# DDR3_2.net
KiCad netlist of a schematic drawn in Altium Designer
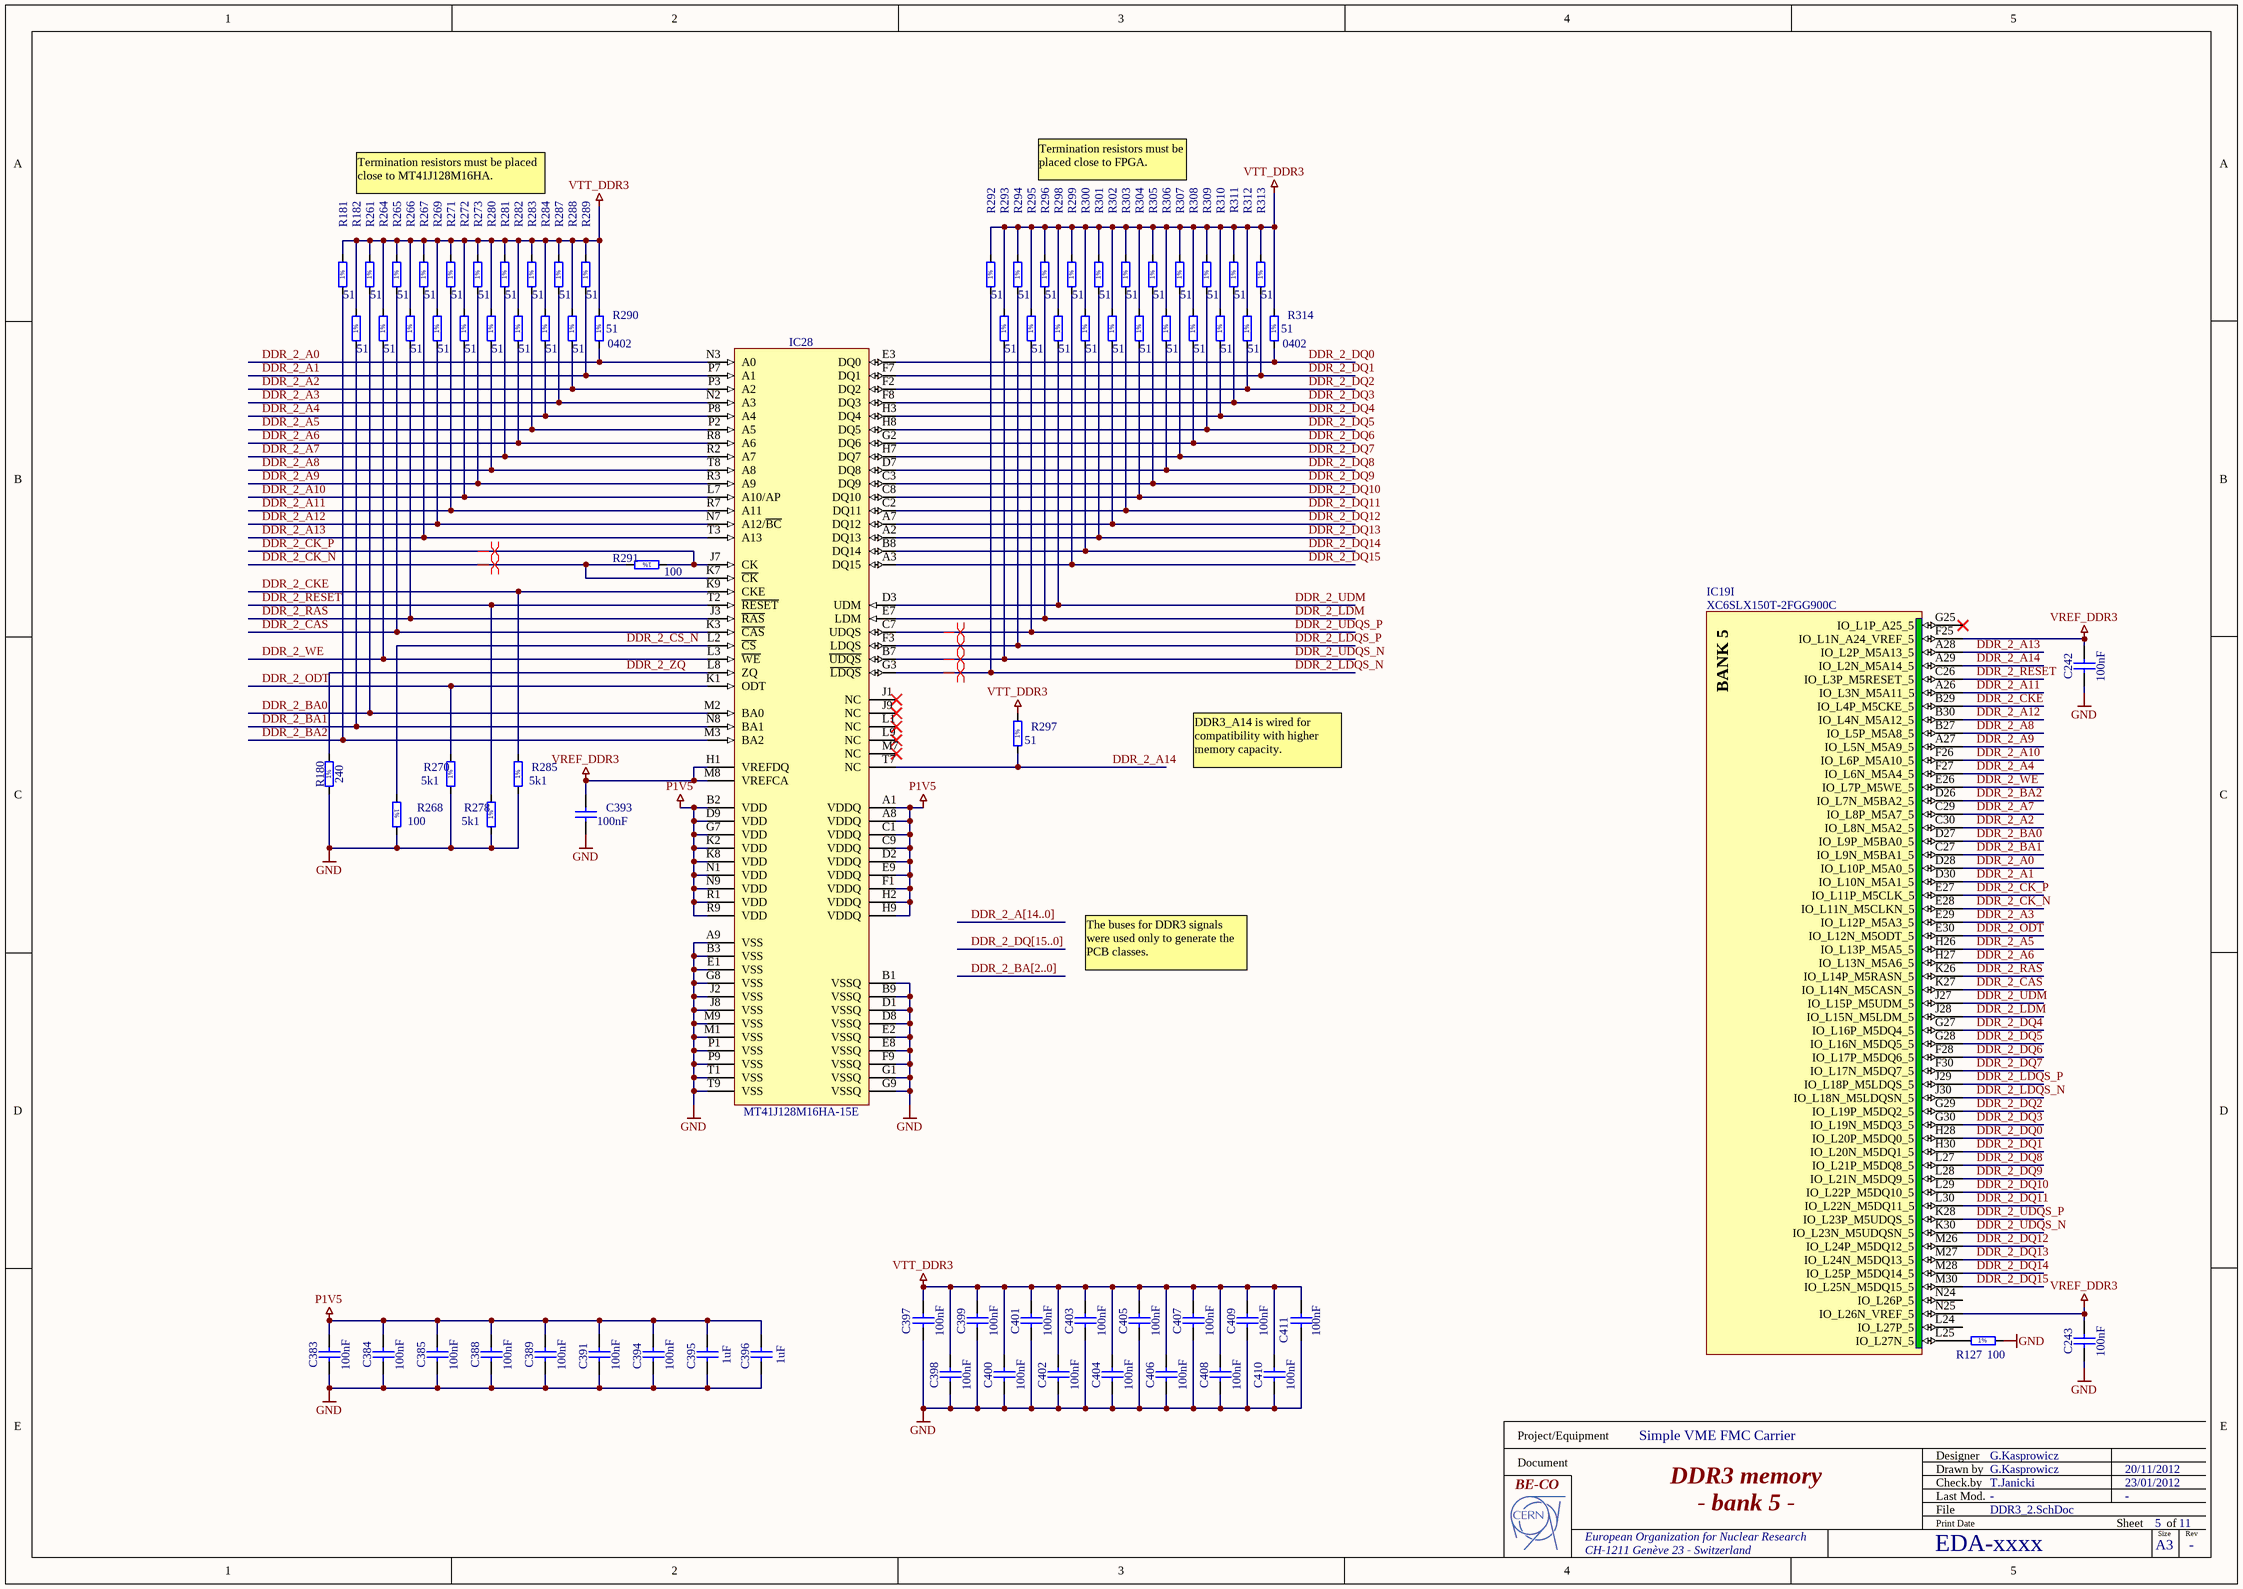
[diagram p0: DDR3_2.SchDoc]

(export (version "E")
  (design (tool "Eeschema 10.0.6"))
  (components
    (comp (ref "C242")
      (value "100nF")
      (footprint "CAPC1005X55N")
      (description "Non-polarised capacitor")
      (fields (field (name "PART NUMBER") "CC0402_100NF_16V_10%_X7R") (field (name "VOLTAGE") "16V"))
      (libsource (lib "Capacitors") (part "Capacitor - non polarized"))
    )
    (comp (ref "C243")
      (value "100nF")
      (footprint "CAPC1005X55N")
      (description "Non-polarised capacitor")
      (fields (field (name "PART NUMBER") "CC0402_100NF_16V_10%_X7R") (field (name "VOLTAGE") "16V"))
      (libsource (lib "Capacitors") (part "Capacitor - non polarized"))
    )
    (comp (ref "C383")
      (value "100nF")
      (footprint "CAPC1005X55N")
      (description "Non-polarised capacitor")
      (fields (field (name "PART NUMBER") "CC0402_100NF_16V_10%_X7R") (field (name "VOLTAGE") "16V"))
      (libsource (lib "Capacitors") (part "Capacitor - non polarized"))
    )
    (comp (ref "C384")
      (value "100nF")
      (footprint "CAPC1005X55N")
      (description "Non-polarised capacitor")
      (fields (field (name "PART NUMBER") "CC0402_100NF_16V_10%_X7R") (field (name "VOLTAGE") "16V"))
      (libsource (lib "Capacitors") (part "Capacitor - non polarized"))
    )
    (comp (ref "C385")
      (value "100nF")
      (footprint "CAPC1005X55N")
      (description "Non-polarised capacitor")
      (fields (field (name "PART NUMBER") "CC0402_100NF_16V_10%_X7R") (field (name "VOLTAGE") "16V"))
      (libsource (lib "Capacitors") (part "Capacitor - non polarized"))
    )
    (comp (ref "C388")
      (value "100nF")
      (footprint "CAPC1005X55N")
      (description "Non-polarised capacitor")
      (fields (field (name "PART NUMBER") "CC0402_100NF_16V_10%_X7R") (field (name "VOLTAGE") "16V"))
      (libsource (lib "Capacitors") (part "Capacitor - non polarized"))
    )
    (comp (ref "C389")
      (value "100nF")
      (footprint "CAPC1005X55N")
      (description "Non-polarised capacitor")
      (fields (field (name "PART NUMBER") "CC0402_100NF_16V_10%_X7R") (field (name "VOLTAGE") "16V"))
      (libsource (lib "Capacitors") (part "Capacitor - non polarized"))
    )
    (comp (ref "C391")
      (value "100nF")
      (footprint "CAPC1005X55N")
      (description "Non-polarised capacitor")
      (fields (field (name "PART NUMBER") "CC0402_100NF_16V_10%_X7R") (field (name "VOLTAGE") "16V"))
      (libsource (lib "Capacitors") (part "Capacitor - non polarized"))
    )
    (comp (ref "C393")
      (value "100nF")
      (footprint "CAPC1005X55N")
      (description "Non-polarised capacitor")
      (fields (field (name "PART NUMBER") "CC0402_100NF_16V_10%_X7R") (field (name "VOLTAGE") "16V"))
      (libsource (lib "Capacitors") (part "Capacitor - non polarized"))
    )
    (comp (ref "C394")
      (value "100nF")
      (footprint "CAPC1005X55N")
      (description "Non-polarised capacitor")
      (fields (field (name "PART NUMBER") "CC0402_100NF_16V_10%_X7R") (field (name "VOLTAGE") "16V"))
      (libsource (lib "Capacitors") (part "Capacitor - non polarized"))
    )
    (comp (ref "C395")
      (value "1uF")
      (footprint "CAPC1608X87N")
      (description "Non-polarised capacitor")
      (fields (field (name "PART NUMBER") "CC0603_1UF_16V_10%_X7R") (field (name "VOLTAGE") "16V"))
      (libsource (lib "Capacitors") (part "Capacitor - non polarized"))
    )
    (comp (ref "C396")
      (value "1uF")
      (footprint "CAPC1608X87N")
      (description "Non-polarised capacitor")
      (fields (field (name "PART NUMBER") "CC0603_1UF_16V_10%_X7R") (field (name "VOLTAGE") "16V"))
      (libsource (lib "Capacitors") (part "Capacitor - non polarized"))
    )
    (comp (ref "C397")
      (value "100nF")
      (footprint "CAPC1005X55N")
      (description "Non-polarised capacitor")
      (fields (field (name "PART NUMBER") "CC0402_100NF_16V_10%_X7R") (field (name "VOLTAGE") "16V"))
      (libsource (lib "Capacitors") (part "Capacitor - non polarized"))
    )
    (comp (ref "C398")
      (value "100nF")
      (footprint "CAPC1005X55N")
      (description "Non-polarised capacitor")
      (fields (field (name "PART NUMBER") "CC0402_100NF_16V_10%_X7R") (field (name "VOLTAGE") "16V"))
      (libsource (lib "Capacitors") (part "Capacitor - non polarized"))
    )
    (comp (ref "C399")
      (value "100nF")
      (footprint "CAPC1005X55N")
      (description "Non-polarised capacitor")
      (fields (field (name "PART NUMBER") "CC0402_100NF_16V_10%_X7R") (field (name "VOLTAGE") "16V"))
      (libsource (lib "Capacitors") (part "Capacitor - non polarized"))
    )
    (comp (ref "C400")
      (value "100nF")
      (footprint "CAPC1005X55N")
      (description "Non-polarised capacitor")
      (fields (field (name "PART NUMBER") "CC0402_100NF_16V_10%_X7R") (field (name "VOLTAGE") "16V"))
      (libsource (lib "Capacitors") (part "Capacitor - non polarized"))
    )
    (comp (ref "C401")
      (value "100nF")
      (footprint "CAPC1005X55N")
      (description "Non-polarised capacitor")
      (fields (field (name "PART NUMBER") "CC0402_100NF_16V_10%_X7R") (field (name "VOLTAGE") "16V"))
      (libsource (lib "Capacitors") (part "Capacitor - non polarized"))
    )
    (comp (ref "C402")
      (value "100nF")
      (footprint "CAPC1005X55N")
      (description "Non-polarised capacitor")
      (fields (field (name "PART NUMBER") "CC0402_100NF_16V_10%_X7R") (field (name "VOLTAGE") "16V"))
      (libsource (lib "Capacitors") (part "Capacitor - non polarized"))
    )
    (comp (ref "C403")
      (value "100nF")
      (footprint "CAPC1005X55N")
      (description "Non-polarised capacitor")
      (fields (field (name "PART NUMBER") "CC0402_100NF_16V_10%_X7R") (field (name "VOLTAGE") "16V"))
      (libsource (lib "Capacitors") (part "Capacitor - non polarized"))
    )
    (comp (ref "C404")
      (value "100nF")
      (footprint "CAPC1005X55N")
      (description "Non-polarised capacitor")
      (fields (field (name "PART NUMBER") "CC0402_100NF_16V_10%_X7R") (field (name "VOLTAGE") "16V"))
      (libsource (lib "Capacitors") (part "Capacitor - non polarized"))
    )
    (comp (ref "C405")
      (value "100nF")
      (footprint "CAPC1005X55N")
      (description "Non-polarised capacitor")
      (fields (field (name "PART NUMBER") "CC0402_100NF_16V_10%_X7R") (field (name "VOLTAGE") "16V"))
      (libsource (lib "Capacitors") (part "Capacitor - non polarized"))
    )
    (comp (ref "C406")
      (value "100nF")
      (footprint "CAPC1005X55N")
      (description "Non-polarised capacitor")
      (fields (field (name "PART NUMBER") "CC0402_100NF_16V_10%_X7R") (field (name "VOLTAGE") "16V"))
      (libsource (lib "Capacitors") (part "Capacitor - non polarized"))
    )
    (comp (ref "C407")
      (value "100nF")
      (footprint "CAPC1005X55N")
      (description "Non-polarised capacitor")
      (fields (field (name "PART NUMBER") "CC0402_100NF_16V_10%_X7R") (field (name "VOLTAGE") "16V"))
      (libsource (lib "Capacitors") (part "Capacitor - non polarized"))
    )
    (comp (ref "C408")
      (value "100nF")
      (footprint "CAPC1005X55N")
      (description "Non-polarised capacitor")
      (fields (field (name "PART NUMBER") "CC0402_100NF_16V_10%_X7R") (field (name "VOLTAGE") "16V"))
      (libsource (lib "Capacitors") (part "Capacitor - non polarized"))
    )
    (comp (ref "C409")
      (value "100nF")
      (footprint "CAPC1005X55N")
      (description "Non-polarised capacitor")
      (fields (field (name "PART NUMBER") "CC0402_100NF_16V_10%_X7R") (field (name "VOLTAGE") "16V"))
      (libsource (lib "Capacitors") (part "Capacitor - non polarized"))
    )
    (comp (ref "C410")
      (value "100nF")
      (footprint "CAPC1005X55N")
      (description "Non-polarised capacitor")
      (fields (field (name "PART NUMBER") "CC0402_100NF_16V_10%_X7R") (field (name "VOLTAGE") "16V"))
      (libsource (lib "Capacitors") (part "Capacitor - non polarized"))
    )
    (comp (ref "C411")
      (value "100nF")
      (footprint "CAPC1005X55N")
      (description "Non-polarised capacitor")
      (fields (field (name "PART NUMBER") "CC0402_100NF_16V_10%_X7R") (field (name "VOLTAGE") "16V"))
      (libsource (lib "Capacitors") (part "Capacitor - non polarized"))
    )
    (comp (ref "IC19")
      (value "XC6SLX150T-2FGG900C")
      (footprint "BGA900C100P30X30_3100X3100X260")
      (description "SPARTAN-6, FPGA, 900-Ball BGA, Commercial Grade, Pb-Free")
      (fields (field (name "MANUFACTURER") "XILINX"))
      (libsource (lib "ICs And Semiconductors") (part "XC6SLX150T-2FGG900C"))
    )
    (comp (ref "IC28")
      (value "MT41J128M16HA-15E")
      (footprint "BGA96C80P9X16_900X1400X120")
      (description "16 Meg x 16 x 8 Banks DDR3 SDRAM")
      (fields (field (name "MANUFACTURER") "MICRON TECHNOLOGY"))
      (libsource (lib "ICs And Semiconductors") (part "MT41J128M16HA"))
    )
    (comp (ref "R127")
      (value "100")
      (footprint "RESC1608X55N")
      (description "Resistor - 1%")
      (fields (field (name "PART NUMBER") "R0603_100R_1%_0.1W_100PPM") (field (name "POWER") "0.1W"))
      (libsource (lib "Resistors") (part "Resistor - 1%"))
    )
    (comp (ref "R180")
      (value "240")
      (footprint "RESC1608X55N")
      (description "Resistor - 1%")
      (fields (field (name "PART NUMBER") "R0603_240R_1%_0.1W_100PPM") (field (name "POWER") "0.1W"))
      (libsource (lib "Resistors") (part "Resistor - 1%"))
    )
    (comp (ref "R181")
      (value "51")
      (footprint "RESC1005X40N")
      (description "Resistor - 1%")
      (fields (field (name "PART NUMBER") "R0402_51R_1%_0.0625W_100PPM") (field (name "POWER") "0.0625W"))
      (libsource (lib "Resistors") (part "Resistor - 1%"))
    )
    (comp (ref "R182")
      (value "51")
      (footprint "RESC1005X40N")
      (description "Resistor - 1%")
      (fields (field (name "PART NUMBER") "R0402_51R_1%_0.0625W_100PPM") (field (name "POWER") "0.0625W"))
      (libsource (lib "Resistors") (part "Resistor - 1%"))
    )
    (comp (ref "R261")
      (value "51")
      (footprint "RESC1005X40N")
      (description "Resistor - 1%")
      (fields (field (name "PART NUMBER") "R0402_51R_1%_0.0625W_100PPM") (field (name "POWER") "0.0625W"))
      (libsource (lib "Resistors") (part "Resistor - 1%"))
    )
    (comp (ref "R264")
      (value "51")
      (footprint "RESC1005X40N")
      (description "Resistor - 1%")
      (fields (field (name "PART NUMBER") "R0402_51R_1%_0.0625W_100PPM") (field (name "POWER") "0.0625W"))
      (libsource (lib "Resistors") (part "Resistor - 1%"))
    )
    (comp (ref "R265")
      (value "51")
      (footprint "RESC1005X40N")
      (description "Resistor - 1%")
      (fields (field (name "PART NUMBER") "R0402_51R_1%_0.0625W_100PPM") (field (name "POWER") "0.0625W"))
      (libsource (lib "Resistors") (part "Resistor - 1%"))
    )
    (comp (ref "R266")
      (value "51")
      (footprint "RESC1005X40N")
      (description "Resistor - 1%")
      (fields (field (name "PART NUMBER") "R0402_51R_1%_0.0625W_100PPM") (field (name "POWER") "0.0625W"))
      (libsource (lib "Resistors") (part "Resistor - 1%"))
    )
    (comp (ref "R267")
      (value "51")
      (footprint "RESC1005X40N")
      (description "Resistor - 1%")
      (fields (field (name "PART NUMBER") "R0402_51R_1%_0.0625W_100PPM") (field (name "POWER") "0.0625W"))
      (libsource (lib "Resistors") (part "Resistor - 1%"))
    )
    (comp (ref "R268")
      (value "100")
      (footprint "RESC1608X55N")
      (description "Resistor - 1%")
      (fields (field (name "PART NUMBER") "R0603_100R_1%_0.1W_100PPM") (field (name "POWER") "0.1W"))
      (libsource (lib "Resistors") (part "Resistor - 1%"))
    )
    (comp (ref "R269")
      (value "51")
      (footprint "RESC1005X40N")
      (description "Resistor - 1%")
      (fields (field (name "PART NUMBER") "R0402_51R_1%_0.0625W_100PPM") (field (name "POWER") "0.0625W"))
      (libsource (lib "Resistors") (part "Resistor - 1%"))
    )
    (comp (ref "R270")
      (value "5k1")
      (footprint "RESC1608X55N")
      (description "Resistor - 1%")
      (fields (field (name "PART NUMBER") "R0603_5K1_1%_0.1W_100PPM") (field (name "POWER") "0.1W"))
      (libsource (lib "Resistors") (part "Resistor - 1%"))
    )
    (comp (ref "R271")
      (value "51")
      (footprint "RESC1005X40N")
      (description "Resistor - 1%")
      (fields (field (name "PART NUMBER") "R0402_51R_1%_0.0625W_100PPM") (field (name "POWER") "0.0625W"))
      (libsource (lib "Resistors") (part "Resistor - 1%"))
    )
    (comp (ref "R272")
      (value "51")
      (footprint "RESC1005X40N")
      (description "Resistor - 1%")
      (fields (field (name "PART NUMBER") "R0402_51R_1%_0.0625W_100PPM") (field (name "POWER") "0.0625W"))
      (libsource (lib "Resistors") (part "Resistor - 1%"))
    )
    (comp (ref "R273")
      (value "51")
      (footprint "RESC1005X40N")
      (description "Resistor - 1%")
      (fields (field (name "PART NUMBER") "R0402_51R_1%_0.0625W_100PPM") (field (name "POWER") "0.0625W"))
      (libsource (lib "Resistors") (part "Resistor - 1%"))
    )
    (comp (ref "R278")
      (value "5k1")
      (footprint "RESC1608X55N")
      (description "Resistor - 1%")
      (fields (field (name "PART NUMBER") "R0603_5K1_1%_0.1W_100PPM") (field (name "POWER") "0.1W"))
      (libsource (lib "Resistors") (part "Resistor - 1%"))
    )
    (comp (ref "R280")
      (value "51")
      (footprint "RESC1005X40N")
      (description "Resistor - 1%")
      (fields (field (name "PART NUMBER") "R0402_51R_1%_0.0625W_100PPM") (field (name "POWER") "0.0625W"))
      (libsource (lib "Resistors") (part "Resistor - 1%"))
    )
    (comp (ref "R281")
      (value "51")
      (footprint "RESC1005X40N")
      (description "Resistor - 1%")
      (fields (field (name "PART NUMBER") "R0402_51R_1%_0.0625W_100PPM") (field (name "POWER") "0.0625W"))
      (libsource (lib "Resistors") (part "Resistor - 1%"))
    )
    (comp (ref "R282")
      (value "51")
      (footprint "RESC1005X40N")
      (description "Resistor - 1%")
      (fields (field (name "PART NUMBER") "R0402_51R_1%_0.0625W_100PPM") (field (name "POWER") "0.0625W"))
      (libsource (lib "Resistors") (part "Resistor - 1%"))
    )
    (comp (ref "R283")
      (value "51")
      (footprint "RESC1005X40N")
      (description "Resistor - 1%")
      (fields (field (name "PART NUMBER") "R0402_51R_1%_0.0625W_100PPM") (field (name "POWER") "0.0625W"))
      (libsource (lib "Resistors") (part "Resistor - 1%"))
    )
    (comp (ref "R284")
      (value "51")
      (footprint "RESC1005X40N")
      (description "Resistor - 1%")
      (fields (field (name "PART NUMBER") "R0402_51R_1%_0.0625W_100PPM") (field (name "POWER") "0.0625W"))
      (libsource (lib "Resistors") (part "Resistor - 1%"))
    )
    (comp (ref "R285")
      (value "5k1")
      (footprint "RESC1608X55N")
      (description "Resistor - 1%")
      (fields (field (name "PART NUMBER") "R0603_5K1_1%_0.1W_100PPM") (field (name "POWER") "0.1W"))
      (libsource (lib "Resistors") (part "Resistor - 1%"))
    )
    (comp (ref "R287")
      (value "51")
      (footprint "RESC1005X40N")
      (description "Resistor - 1%")
      (fields (field (name "PART NUMBER") "R0402_51R_1%_0.0625W_100PPM") (field (name "POWER") "0.0625W"))
      (libsource (lib "Resistors") (part "Resistor - 1%"))
    )
    (comp (ref "R288")
      (value "51")
      (footprint "RESC1005X40N")
      (description "Resistor - 1%")
      (fields (field (name "PART NUMBER") "R0402_51R_1%_0.0625W_100PPM") (field (name "POWER") "0.0625W"))
      (libsource (lib "Resistors") (part "Resistor - 1%"))
    )
    (comp (ref "R289")
      (value "51")
      (footprint "RESC1005X40N")
      (description "Resistor - 1%")
      (fields (field (name "PART NUMBER") "R0402_51R_1%_0.0625W_100PPM") (field (name "POWER") "0.0625W"))
      (libsource (lib "Resistors") (part "Resistor - 1%"))
    )
    (comp (ref "R290")
      (value "51")
      (footprint "RESC1005X40N")
      (description "Resistor - 1%")
      (fields
        (field (name "PART NUMBER") "R0402_51R_1%_0.0625W_100PPM")
        (field (name "POWER") "0.0625W")
        (field (name "CASE") "0402")
      )
      (libsource (lib "Resistors") (part "Resistor - 1%"))
    )
    (comp (ref "R291")
      (value "100")
      (footprint "RESC1608X55N")
      (description "Resistor - 1%")
      (fields (field (name "PART NUMBER") "R0603_100R_1%_0.1W_100PPM") (field (name "POWER") "0.1W"))
      (libsource (lib "Resistors") (part "Resistor - 1%"))
    )
    (comp (ref "R292")
      (value "51")
      (footprint "RESC1005X40N")
      (description "Resistor - 1%")
      (fields (field (name "PART NUMBER") "R0402_51R_1%_0.0625W_100PPM") (field (name "POWER") "0.0625W"))
      (libsource (lib "Resistors") (part "Resistor - 1%"))
    )
    (comp (ref "R293")
      (value "51")
      (footprint "RESC1005X40N")
      (description "Resistor - 1%")
      (fields (field (name "PART NUMBER") "R0402_51R_1%_0.0625W_100PPM") (field (name "POWER") "0.0625W"))
      (libsource (lib "Resistors") (part "Resistor - 1%"))
    )
    (comp (ref "R294")
      (value "51")
      (footprint "RESC1005X40N")
      (description "Resistor - 1%")
      (fields (field (name "PART NUMBER") "R0402_51R_1%_0.0625W_100PPM") (field (name "POWER") "0.0625W"))
      (libsource (lib "Resistors") (part "Resistor - 1%"))
    )
    (comp (ref "R295")
      (value "51")
      (footprint "RESC1005X40N")
      (description "Resistor - 1%")
      (fields (field (name "PART NUMBER") "R0402_51R_1%_0.0625W_100PPM") (field (name "POWER") "0.0625W"))
      (libsource (lib "Resistors") (part "Resistor - 1%"))
    )
    (comp (ref "R296")
      (value "51")
      (footprint "RESC1005X40N")
      (description "Resistor - 1%")
      (fields (field (name "PART NUMBER") "R0402_51R_1%_0.0625W_100PPM") (field (name "POWER") "0.0625W"))
      (libsource (lib "Resistors") (part "Resistor - 1%"))
    )
    (comp (ref "R297")
      (value "51")
      (footprint "RESC1005X40N")
      (description "Resistor - 1%")
      (fields (field (name "PART NUMBER") "R0402_51R_1%_0.0625W_100PPM") (field (name "POWER") "0.0625W"))
      (libsource (lib "Resistors") (part "Resistor - 1%"))
    )
    (comp (ref "R298")
      (value "51")
      (footprint "RESC1005X40N")
      (description "Resistor - 1%")
      (fields (field (name "PART NUMBER") "R0402_51R_1%_0.0625W_100PPM") (field (name "POWER") "0.0625W"))
      (libsource (lib "Resistors") (part "Resistor - 1%"))
    )
    (comp (ref "R299")
      (value "51")
      (footprint "RESC1005X40N")
      (description "Resistor - 1%")
      (fields (field (name "PART NUMBER") "R0402_51R_1%_0.0625W_100PPM") (field (name "POWER") "0.0625W"))
      (libsource (lib "Resistors") (part "Resistor - 1%"))
    )
    (comp (ref "R300")
      (value "51")
      (footprint "RESC1005X40N")
      (description "Resistor - 1%")
      (fields (field (name "PART NUMBER") "R0402_51R_1%_0.0625W_100PPM") (field (name "POWER") "0.0625W"))
      (libsource (lib "Resistors") (part "Resistor - 1%"))
    )
    (comp (ref "R301")
      (value "51")
      (footprint "RESC1005X40N")
      (description "Resistor - 1%")
      (fields (field (name "PART NUMBER") "R0402_51R_1%_0.0625W_100PPM") (field (name "POWER") "0.0625W"))
      (libsource (lib "Resistors") (part "Resistor - 1%"))
    )
    (comp (ref "R302")
      (value "51")
      (footprint "RESC1005X40N")
      (description "Resistor - 1%")
      (fields (field (name "PART NUMBER") "R0402_51R_1%_0.0625W_100PPM") (field (name "POWER") "0.0625W"))
      (libsource (lib "Resistors") (part "Resistor - 1%"))
    )
    (comp (ref "R303")
      (value "51")
      (footprint "RESC1005X40N")
      (description "Resistor - 1%")
      (fields (field (name "PART NUMBER") "R0402_51R_1%_0.0625W_100PPM") (field (name "POWER") "0.0625W"))
      (libsource (lib "Resistors") (part "Resistor - 1%"))
    )
    (comp (ref "R304")
      (value "51")
      (footprint "RESC1005X40N")
      (description "Resistor - 1%")
      (fields (field (name "PART NUMBER") "R0402_51R_1%_0.0625W_100PPM") (field (name "POWER") "0.0625W"))
      (libsource (lib "Resistors") (part "Resistor - 1%"))
    )
    (comp (ref "R305")
      (value "51")
      (footprint "RESC1005X40N")
      (description "Resistor - 1%")
      (fields (field (name "PART NUMBER") "R0402_51R_1%_0.0625W_100PPM") (field (name "POWER") "0.0625W"))
      (libsource (lib "Resistors") (part "Resistor - 1%"))
    )
    (comp (ref "R306")
      (value "51")
      (footprint "RESC1005X40N")
      (description "Resistor - 1%")
      (fields (field (name "PART NUMBER") "R0402_51R_1%_0.0625W_100PPM") (field (name "POWER") "0.0625W"))
      (libsource (lib "Resistors") (part "Resistor - 1%"))
    )
    (comp (ref "R307")
      (value "51")
      (footprint "RESC1005X40N")
      (description "Resistor - 1%")
      (fields (field (name "PART NUMBER") "R0402_51R_1%_0.0625W_100PPM") (field (name "POWER") "0.0625W"))
      (libsource (lib "Resistors") (part "Resistor - 1%"))
    )
    (comp (ref "R308")
      (value "51")
      (footprint "RESC1005X40N")
      (description "Resistor - 1%")
      (fields (field (name "PART NUMBER") "R0402_51R_1%_0.0625W_100PPM") (field (name "POWER") "0.0625W"))
      (libsource (lib "Resistors") (part "Resistor - 1%"))
    )
    (comp (ref "R309")
      (value "51")
      (footprint "RESC1005X40N")
      (description "Resistor - 1%")
      (fields (field (name "PART NUMBER") "R0402_51R_1%_0.0625W_100PPM") (field (name "POWER") "0.0625W"))
      (libsource (lib "Resistors") (part "Resistor - 1%"))
    )
    (comp (ref "R310")
      (value "51")
      (footprint "RESC1005X40N")
      (description "Resistor - 1%")
      (fields (field (name "PART NUMBER") "R0402_51R_1%_0.0625W_100PPM") (field (name "POWER") "0.0625W"))
      (libsource (lib "Resistors") (part "Resistor - 1%"))
    )
    (comp (ref "R311")
      (value "51")
      (footprint "RESC1005X40N")
      (description "Resistor - 1%")
      (fields (field (name "PART NUMBER") "R0402_51R_1%_0.0625W_100PPM") (field (name "POWER") "0.0625W"))
      (libsource (lib "Resistors") (part "Resistor - 1%"))
    )
    (comp (ref "R312")
      (value "51")
      (footprint "RESC1005X40N")
      (description "Resistor - 1%")
      (fields (field (name "PART NUMBER") "R0402_51R_1%_0.0625W_100PPM") (field (name "POWER") "0.0625W"))
      (libsource (lib "Resistors") (part "Resistor - 1%"))
    )
    (comp (ref "R313")
      (value "51")
      (footprint "RESC1005X40N")
      (description "Resistor - 1%")
      (fields (field (name "PART NUMBER") "R0402_51R_1%_0.0625W_100PPM") (field (name "POWER") "0.0625W"))
      (libsource (lib "Resistors") (part "Resistor - 1%"))
    )
    (comp (ref "R314")
      (value "51")
      (footprint "RESC1005X40N")
      (description "Resistor - 1%")
      (fields
        (field (name "PART NUMBER") "R0402_51R_1%_0.0625W_100PPM")
        (field (name "POWER") "0.0625W")
        (field (name "CASE") "0402")
      )
      (libsource (lib "Resistors") (part "Resistor - 1%"))
    )
  )
  (nets
    (net (code "1") (name "/DDR_2_A0") (class "Default")
      (node (ref "IC19") (pin "D28") (pinfunction "IO_L10P_M5A0_5_D28") (pintype "bidirectional"))
      (node (ref "IC28") (pin "N3") (pinfunction "A0_N3") (pintype "input"))
      (node (ref "R290") (pin "1") (pinfunction "1_1") (pintype "passive"))
    )
    (net (code "2") (name "/DDR_2_A1") (class "Default")
      (node (ref "IC19") (pin "D30") (pinfunction "IO_L10N_M5A1_5_D30") (pintype "bidirectional"))
      (node (ref "IC28") (pin "P7") (pinfunction "A1_P7") (pintype "input"))
      (node (ref "R289") (pin "1") (pinfunction "1_1") (pintype "passive"))
    )
    (net (code "3") (name "/DDR_2_A2") (class "Default")
      (node (ref "IC19") (pin "C30") (pinfunction "IO_L8N_M5A2_5_C30") (pintype "bidirectional"))
      (node (ref "IC28") (pin "P3") (pinfunction "A2_P3") (pintype "input"))
      (node (ref "R288") (pin "1") (pinfunction "1_1") (pintype "passive"))
    )
    (net (code "4") (name "/DDR_2_A3") (class "Default")
      (node (ref "IC19") (pin "E29") (pinfunction "IO_L12P_M5A3_5_E29") (pintype "bidirectional"))
      (node (ref "IC28") (pin "N2") (pinfunction "A3_N2") (pintype "input"))
      (node (ref "R287") (pin "1") (pinfunction "1_1") (pintype "passive"))
    )
    (net (code "5") (name "/DDR_2_A4") (class "Default")
      (node (ref "IC19") (pin "F27") (pinfunction "IO_L6N_M5A4_5_F27") (pintype "bidirectional"))
      (node (ref "IC28") (pin "P8") (pinfunction "A4_P8") (pintype "input"))
      (node (ref "R284") (pin "1") (pinfunction "1_1") (pintype "passive"))
    )
    (net (code "6") (name "/DDR_2_A5") (class "Default")
      (node (ref "IC19") (pin "H26") (pinfunction "IO_L13P_M5A5_5_H26") (pintype "bidirectional"))
      (node (ref "IC28") (pin "P2") (pinfunction "A5_P2") (pintype "input"))
      (node (ref "R283") (pin "1") (pinfunction "1_1") (pintype "passive"))
    )
    (net (code "7") (name "/DDR_2_A6") (class "Default")
      (node (ref "IC19") (pin "H27") (pinfunction "IO_L13N_M5A6_5_H27") (pintype "bidirectional"))
      (node (ref "IC28") (pin "R8") (pinfunction "A6_R8") (pintype "input"))
      (node (ref "R282") (pin "1") (pinfunction "1_1") (pintype "passive"))
    )
    (net (code "8") (name "/DDR_2_A7") (class "Default")
      (node (ref "IC19") (pin "C29") (pinfunction "IO_L8P_M5A7_5_C29") (pintype "bidirectional"))
      (node (ref "IC28") (pin "R2") (pinfunction "A7_R2") (pintype "input"))
      (node (ref "R281") (pin "1") (pinfunction "1_1") (pintype "passive"))
    )
    (net (code "9") (name "/DDR_2_A8") (class "Default")
      (node (ref "IC19") (pin "B27") (pinfunction "IO_L5P_M5A8_5_B27") (pintype "bidirectional"))
      (node (ref "IC28") (pin "T8") (pinfunction "A8_T8") (pintype "input"))
      (node (ref "R280") (pin "1") (pinfunction "1_1") (pintype "passive"))
    )
    (net (code "10") (name "/DDR_2_A9") (class "Default")
      (node (ref "IC19") (pin "A27") (pinfunction "IO_L5N_M5A9_5_A27") (pintype "bidirectional"))
      (node (ref "IC28") (pin "R3") (pinfunction "A9_R3") (pintype "input"))
      (node (ref "R273") (pin "1") (pinfunction "1_1") (pintype "passive"))
    )
    (net (code "11") (name "/DDR_2_A10") (class "Default")
      (node (ref "IC19") (pin "F26") (pinfunction "IO_L6P_M5A10_5_F26") (pintype "bidirectional"))
      (node (ref "IC28") (pin "L7") (pinfunction "A10/AP_L7") (pintype "input"))
      (node (ref "R272") (pin "1") (pinfunction "1_1") (pintype "passive"))
    )
    (net (code "12") (name "/DDR_2_A11") (class "Default")
      (node (ref "IC19") (pin "A26") (pinfunction "IO_L3N_M5A11_5_A26") (pintype "bidirectional"))
      (node (ref "IC28") (pin "R7") (pinfunction "A11_R7") (pintype "input"))
      (node (ref "R271") (pin "1") (pinfunction "1_1") (pintype "passive"))
    )
    (net (code "13") (name "/DDR_2_A12") (class "Default")
      (node (ref "IC19") (pin "B30") (pinfunction "IO_L4N_M5A12_5_B30") (pintype "bidirectional"))
      (node (ref "IC28") (pin "N7") (pinfunction "A12/~{BC}_N7") (pintype "input"))
      (node (ref "R269") (pin "1") (pinfunction "1_1") (pintype "passive"))
    )
    (net (code "14") (name "/DDR_2_A13") (class "Default")
      (node (ref "IC19") (pin "A28") (pinfunction "IO_L2P_M5A13_5_A28") (pintype "bidirectional"))
      (node (ref "IC28") (pin "T3") (pinfunction "A13_T3") (pintype "input"))
      (node (ref "R267") (pin "1") (pinfunction "1_1") (pintype "passive"))
    )
    (net (code "15") (name "/DDR_2_A14") (class "Default")
      (node (ref "IC19") (pin "A29") (pinfunction "IO_L2N_M5A14_5_A29") (pintype "bidirectional"))
      (node (ref "IC28") (pin "T7") (pinfunction "NC_T7") (pintype "passive"))
      (node (ref "R297") (pin "1") (pinfunction "1_1") (pintype "passive"))
    )
    (net (code "17") (name "/DDR_2_BA0") (class "Default")
      (node (ref "IC19") (pin "D27") (pinfunction "IO_L9P_M5BA0_5_D27") (pintype "bidirectional"))
      (node (ref "IC28") (pin "M2") (pinfunction "BA0_M2") (pintype "input"))
      (node (ref "R261") (pin "1") (pinfunction "1_1") (pintype "passive"))
    )
    (net (code "18") (name "/DDR_2_BA1") (class "Default")
      (node (ref "IC19") (pin "C27") (pinfunction "IO_L9N_M5BA1_5_C27") (pintype "bidirectional"))
      (node (ref "IC28") (pin "N8") (pinfunction "BA1_N8") (pintype "input"))
      (node (ref "R182") (pin "1") (pinfunction "1_1") (pintype "passive"))
    )
    (net (code "19") (name "/DDR_2_BA2") (class "Default")
      (node (ref "IC19") (pin "D26") (pinfunction "IO_L7N_M5BA2_5_D26") (pintype "bidirectional"))
      (node (ref "IC28") (pin "M3") (pinfunction "BA2_M3") (pintype "input"))
      (node (ref "R181") (pin "1") (pinfunction "1_1") (pintype "passive"))
    )
    (net (code "21") (name "/DDR_2_CAS") (class "Default")
      (node (ref "IC19") (pin "K27") (pinfunction "IO_L14N_M5CASN_5_K27") (pintype "bidirectional"))
      (node (ref "IC28") (pin "K3") (pinfunction "CAS_K3") (pintype "input"))
      (node (ref "R265") (pin "1") (pinfunction "1_1") (pintype "passive"))
    )
    (net (code "22") (name "/DDR_2_CKE") (class "Default")
      (node (ref "IC19") (pin "B29") (pinfunction "IO_L4P_M5CKE_5_B29") (pintype "bidirectional"))
      (node (ref "IC28") (pin "K9") (pinfunction "CKE_K9") (pintype "input"))
      (node (ref "R285") (pin "2") (pinfunction "2_2") (pintype "passive"))
    )
    (net (code "23") (name "/DDR_2_CK_N") (class "Default")
      (node (ref "IC19") (pin "E28") (pinfunction "IO_L11N_M5CLKN_5_E28") (pintype "bidirectional"))
      (node (ref "IC28") (pin "K7") (pinfunction "CK_K7") (pintype "input"))
      (node (ref "R291") (pin "2") (pinfunction "2_2") (pintype "passive"))
    )
    (net (code "24") (name "/DDR_2_CK_P") (class "Default")
      (node (ref "IC19") (pin "E27") (pinfunction "IO_L11P_M5CLK_5_E27") (pintype "bidirectional"))
      (node (ref "IC28") (pin "J7") (pinfunction "CK_J7") (pintype "input"))
      (node (ref "R291") (pin "1") (pinfunction "1_1") (pintype "passive"))
    )
    (net (code "25") (name "/DDR_2_CS_N") (class "Default")
      (node (ref "IC28") (pin "L2") (pinfunction "CS_L2") (pintype "input"))
      (node (ref "R268") (pin "1") (pinfunction "1_1") (pintype "passive"))
    )
    (net (code "26") (name "/DDR_2_DQ0") (class "Default")
      (node (ref "IC19") (pin "H28") (pinfunction "IO_L20P_M5DQ0_5_H28") (pintype "bidirectional"))
      (node (ref "IC28") (pin "E3") (pinfunction "DQ0_E3") (pintype "bidirectional"))
      (node (ref "R314") (pin "1") (pinfunction "1_1") (pintype "passive"))
    )
    (net (code "27") (name "/DDR_2_DQ1") (class "Default")
      (node (ref "IC19") (pin "H30") (pinfunction "IO_L20N_M5DQ1_5_H30") (pintype "bidirectional"))
      (node (ref "IC28") (pin "F7") (pinfunction "DQ1_F7") (pintype "bidirectional"))
      (node (ref "R313") (pin "1") (pinfunction "1_1") (pintype "passive"))
    )
    (net (code "28") (name "/DDR_2_DQ2") (class "Default")
      (node (ref "IC19") (pin "G29") (pinfunction "IO_L19P_M5DQ2_5_G29") (pintype "bidirectional"))
      (node (ref "IC28") (pin "F2") (pinfunction "DQ2_F2") (pintype "bidirectional"))
      (node (ref "R312") (pin "1") (pinfunction "1_1") (pintype "passive"))
    )
    (net (code "29") (name "/DDR_2_DQ3") (class "Default")
      (node (ref "IC19") (pin "G30") (pinfunction "IO_L19N_M5DQ3_5_G30") (pintype "bidirectional"))
      (node (ref "IC28") (pin "F8") (pinfunction "DQ3_F8") (pintype "bidirectional"))
      (node (ref "R311") (pin "1") (pinfunction "1_1") (pintype "passive"))
    )
    (net (code "30") (name "/DDR_2_DQ4") (class "Default")
      (node (ref "IC19") (pin "G27") (pinfunction "IO_L16P_M5DQ4_5_G27") (pintype "bidirectional"))
      (node (ref "IC28") (pin "H3") (pinfunction "DQ4_H3") (pintype "bidirectional"))
      (node (ref "R310") (pin "1") (pinfunction "1_1") (pintype "passive"))
    )
    (net (code "31") (name "/DDR_2_DQ5") (class "Default")
      (node (ref "IC19") (pin "G28") (pinfunction "IO_L16N_M5DQ5_5_G28") (pintype "bidirectional"))
      (node (ref "IC28") (pin "H8") (pinfunction "DQ5_H8") (pintype "bidirectional"))
      (node (ref "R309") (pin "1") (pinfunction "1_1") (pintype "passive"))
    )
    (net (code "32") (name "/DDR_2_DQ6") (class "Default")
      (node (ref "IC19") (pin "F28") (pinfunction "IO_L17P_M5DQ6_5_F28") (pintype "bidirectional"))
      (node (ref "IC28") (pin "G2") (pinfunction "DQ6_G2") (pintype "bidirectional"))
      (node (ref "R308") (pin "1") (pinfunction "1_1") (pintype "passive"))
    )
    (net (code "33") (name "/DDR_2_DQ7") (class "Default")
      (node (ref "IC19") (pin "F30") (pinfunction "IO_L17N_M5DQ7_5_F30") (pintype "bidirectional"))
      (node (ref "IC28") (pin "H7") (pinfunction "DQ7_H7") (pintype "bidirectional"))
      (node (ref "R307") (pin "1") (pinfunction "1_1") (pintype "passive"))
    )
    (net (code "34") (name "/DDR_2_DQ8") (class "Default")
      (node (ref "IC19") (pin "L27") (pinfunction "IO_L21P_M5DQ8_5_L27") (pintype "bidirectional"))
      (node (ref "IC28") (pin "D7") (pinfunction "DQ8_D7") (pintype "bidirectional"))
      (node (ref "R306") (pin "1") (pinfunction "1_1") (pintype "passive"))
    )
    (net (code "35") (name "/DDR_2_DQ9") (class "Default")
      (node (ref "IC19") (pin "L28") (pinfunction "IO_L21N_M5DQ9_5_L28") (pintype "bidirectional"))
      (node (ref "IC28") (pin "C3") (pinfunction "DQ9_C3") (pintype "bidirectional"))
      (node (ref "R305") (pin "1") (pinfunction "1_1") (pintype "passive"))
    )
    (net (code "36") (name "/DDR_2_DQ10") (class "Default")
      (node (ref "IC19") (pin "L29") (pinfunction "IO_L22P_M5DQ10_5_L29") (pintype "bidirectional"))
      (node (ref "IC28") (pin "C8") (pinfunction "DQ10_C8") (pintype "bidirectional"))
      (node (ref "R304") (pin "1") (pinfunction "1_1") (pintype "passive"))
    )
    (net (code "37") (name "/DDR_2_DQ11") (class "Default")
      (node (ref "IC19") (pin "L30") (pinfunction "IO_L22N_M5DQ11_5_L30") (pintype "bidirectional"))
      (node (ref "IC28") (pin "C2") (pinfunction "DQ11_C2") (pintype "bidirectional"))
      (node (ref "R303") (pin "1") (pinfunction "1_1") (pintype "passive"))
    )
    (net (code "38") (name "/DDR_2_DQ12") (class "Default")
      (node (ref "IC19") (pin "M26") (pinfunction "IO_L24P_M5DQ12_5_M26") (pintype "bidirectional"))
      (node (ref "IC28") (pin "A7") (pinfunction "DQ12_A7") (pintype "bidirectional"))
      (node (ref "R302") (pin "1") (pinfunction "1_1") (pintype "passive"))
    )
    (net (code "39") (name "/DDR_2_DQ13") (class "Default")
      (node (ref "IC19") (pin "M27") (pinfunction "IO_L24N_M5DQ13_5_M27") (pintype "bidirectional"))
      (node (ref "IC28") (pin "A2") (pinfunction "DQ13_A2") (pintype "bidirectional"))
      (node (ref "R301") (pin "1") (pinfunction "1_1") (pintype "passive"))
    )
    (net (code "40") (name "/DDR_2_DQ14") (class "Default")
      (node (ref "IC19") (pin "M28") (pinfunction "IO_L25P_M5DQ14_5_M28") (pintype "bidirectional"))
      (node (ref "IC28") (pin "B8") (pinfunction "DQ14_B8") (pintype "bidirectional"))
      (node (ref "R300") (pin "1") (pinfunction "1_1") (pintype "passive"))
    )
    (net (code "41") (name "/DDR_2_DQ15") (class "Default")
      (node (ref "IC19") (pin "M30") (pinfunction "IO_L25N_M5DQ15_5_M30") (pintype "bidirectional"))
      (node (ref "IC28") (pin "A3") (pinfunction "DQ15_A3") (pintype "bidirectional"))
      (node (ref "R299") (pin "1") (pinfunction "1_1") (pintype "passive"))
    )
    (net (code "43") (name "/DDR_2_LDM") (class "Default")
      (node (ref "IC19") (pin "J28") (pinfunction "IO_L15N_M5LDM_5_J28") (pintype "bidirectional"))
      (node (ref "IC28") (pin "E7") (pinfunction "LDM_E7") (pintype "input"))
      (node (ref "R296") (pin "1") (pinfunction "1_1") (pintype "passive"))
    )
    (net (code "44") (name "/DDR_2_LDQS_N") (class "Default")
      (node (ref "IC19") (pin "J30") (pinfunction "IO_L18N_M5LDQSN_5_J30") (pintype "bidirectional"))
      (node (ref "IC28") (pin "G3") (pinfunction "LDQS_G3") (pintype "bidirectional"))
      (node (ref "R292") (pin "1") (pinfunction "1_1") (pintype "passive"))
    )
    (net (code "45") (name "/DDR_2_LDQS_P") (class "Default")
      (node (ref "IC19") (pin "J29") (pinfunction "IO_L18P_M5LDQS_5_J29") (pintype "bidirectional"))
      (node (ref "IC28") (pin "F3") (pinfunction "LDQS_F3") (pintype "bidirectional"))
      (node (ref "R294") (pin "1") (pinfunction "1_1") (pintype "passive"))
    )
    (net (code "46") (name "/DDR_2_ODT") (class "Default")
      (node (ref "IC19") (pin "E30") (pinfunction "IO_L12N_M5ODT_5_E30") (pintype "bidirectional"))
      (node (ref "IC28") (pin "K1") (pinfunction "ODT_K1") (pintype "input"))
      (node (ref "R270") (pin "2") (pinfunction "2_2") (pintype "passive"))
    )
    (net (code "47") (name "/DDR_2_RAS") (class "Default")
      (node (ref "IC19") (pin "K26") (pinfunction "IO_L14P_M5RASN_5_K26") (pintype "bidirectional"))
      (node (ref "IC28") (pin "J3") (pinfunction "RAS_J3") (pintype "input"))
      (node (ref "R266") (pin "1") (pinfunction "1_1") (pintype "passive"))
    )
    (net (code "48") (name "/DDR_2_RESET") (class "Default")
      (node (ref "IC19") (pin "C26") (pinfunction "IO_L3P_M5RESET_5_C26") (pintype "bidirectional"))
      (node (ref "IC28") (pin "T2") (pinfunction "RESET_T2") (pintype "input"))
      (node (ref "R278") (pin "2") (pinfunction "2_2") (pintype "passive"))
    )
    (net (code "49") (name "/DDR_2_UDM") (class "Default")
      (node (ref "IC19") (pin "J27") (pinfunction "IO_L15P_M5UDM_5_J27") (pintype "bidirectional"))
      (node (ref "IC28") (pin "D3") (pinfunction "UDM_D3") (pintype "input"))
      (node (ref "R298") (pin "1") (pinfunction "1_1") (pintype "passive"))
    )
    (net (code "50") (name "/DDR_2_UDQS_N") (class "Default")
      (node (ref "IC19") (pin "K30") (pinfunction "IO_L23N_M5UDQSN_5_K30") (pintype "bidirectional"))
      (node (ref "IC28") (pin "B7") (pinfunction "UDQS_B7") (pintype "bidirectional"))
      (node (ref "R293") (pin "1") (pinfunction "1_1") (pintype "passive"))
    )
    (net (code "51") (name "/DDR_2_UDQS_P") (class "Default")
      (node (ref "IC19") (pin "K28") (pinfunction "IO_L23P_M5UDQS_5_K28") (pintype "bidirectional"))
      (node (ref "IC28") (pin "C7") (pinfunction "UDQS_C7") (pintype "bidirectional"))
      (node (ref "R295") (pin "1") (pinfunction "1_1") (pintype "passive"))
    )
    (net (code "52") (name "/DDR_2_WE") (class "Default")
      (node (ref "IC19") (pin "E26") (pinfunction "IO_L7P_M5WE_5_E26") (pintype "bidirectional"))
      (node (ref "IC28") (pin "L3") (pinfunction "WE_L3") (pintype "input"))
      (node (ref "R264") (pin "1") (pinfunction "1_1") (pintype "passive"))
    )
    (net (code "53") (name "/DDR_2_ZQ") (class "Default")
      (node (ref "IC28") (pin "L8") (pinfunction "ZQ_L8") (pintype "input"))
      (node (ref "R180") (pin "2") (pinfunction "2_2") (pintype "passive"))
    )
    (net (code "54") (name "GND") (class "Default")
      (node (ref "C242") (pin "1") (pinfunction "1_1") (pintype "passive"))
      (node (ref "C243") (pin "1") (pinfunction "1_1") (pintype "passive"))
      (node (ref "C383") (pin "1") (pinfunction "1_1") (pintype "passive"))
      (node (ref "C384") (pin "1") (pinfunction "1_1") (pintype "passive"))
      (node (ref "C385") (pin "1") (pinfunction "1_1") (pintype "passive"))
      (node (ref "C388") (pin "1") (pinfunction "1_1") (pintype "passive"))
      (node (ref "C389") (pin "1") (pinfunction "1_1") (pintype "passive"))
      (node (ref "C391") (pin "1") (pinfunction "1_1") (pintype "passive"))
      (node (ref "C393") (pin "1") (pinfunction "1_1") (pintype "passive"))
      (node (ref "C394") (pin "1") (pinfunction "1_1") (pintype "passive"))
      (node (ref "C395") (pin "1") (pinfunction "1_1") (pintype "passive"))
      (node (ref "C396") (pin "1") (pinfunction "1_1") (pintype "passive"))
      (node (ref "C397") (pin "1") (pinfunction "1_1") (pintype "passive"))
      (node (ref "C398") (pin "1") (pinfunction "1_1") (pintype "passive"))
      (node (ref "C399") (pin "1") (pinfunction "1_1") (pintype "passive"))
      (node (ref "C400") (pin "1") (pinfunction "1_1") (pintype "passive"))
      (node (ref "C401") (pin "1") (pinfunction "1_1") (pintype "passive"))
      (node (ref "C402") (pin "1") (pinfunction "1_1") (pintype "passive"))
      (node (ref "C403") (pin "1") (pinfunction "1_1") (pintype "passive"))
      (node (ref "C404") (pin "1") (pinfunction "1_1") (pintype "passive"))
      (node (ref "C405") (pin "1") (pinfunction "1_1") (pintype "passive"))
      (node (ref "C406") (pin "1") (pinfunction "1_1") (pintype "passive"))
      (node (ref "C407") (pin "1") (pinfunction "1_1") (pintype "passive"))
      (node (ref "C408") (pin "1") (pinfunction "1_1") (pintype "passive"))
      (node (ref "C409") (pin "1") (pinfunction "1_1") (pintype "passive"))
      (node (ref "C410") (pin "1") (pinfunction "1_1") (pintype "passive"))
      (node (ref "C411") (pin "1") (pinfunction "1_1") (pintype "passive"))
      (node (ref "IC28") (pin "A9") (pinfunction "VSS_A9") (pintype "power_in"))
      (node (ref "IC28") (pin "B1") (pinfunction "VSSQ_B1") (pintype "power_in"))
      (node (ref "IC28") (pin "B3") (pinfunction "VSS_B3") (pintype "power_in"))
      (node (ref "IC28") (pin "B9") (pinfunction "VSSQ_B9") (pintype "power_in"))
      (node (ref "IC28") (pin "D1") (pinfunction "VSSQ_D1") (pintype "power_in"))
      (node (ref "IC28") (pin "D8") (pinfunction "VSSQ_D8") (pintype "power_in"))
      (node (ref "IC28") (pin "E1") (pinfunction "VSS_E1") (pintype "power_in"))
      (node (ref "IC28") (pin "E2") (pinfunction "VSSQ_E2") (pintype "power_in"))
      (node (ref "IC28") (pin "E8") (pinfunction "VSSQ_E8") (pintype "power_in"))
      (node (ref "IC28") (pin "F9") (pinfunction "VSSQ_F9") (pintype "power_in"))
      (node (ref "IC28") (pin "G1") (pinfunction "VSSQ_G1") (pintype "power_in"))
      (node (ref "IC28") (pin "G8") (pinfunction "VSS_G8") (pintype "power_in"))
      (node (ref "IC28") (pin "G9") (pinfunction "VSSQ_G9") (pintype "power_in"))
      (node (ref "IC28") (pin "J2") (pinfunction "VSS_J2") (pintype "power_in"))
      (node (ref "IC28") (pin "J8") (pinfunction "VSS_J8") (pintype "power_in"))
      (node (ref "IC28") (pin "M1") (pinfunction "VSS_M1") (pintype "power_in"))
      (node (ref "IC28") (pin "M9") (pinfunction "VSS_M9") (pintype "power_in"))
      (node (ref "IC28") (pin "P1") (pinfunction "VSS_P1") (pintype "power_in"))
      (node (ref "IC28") (pin "P9") (pinfunction "VSS_P9") (pintype "power_in"))
      (node (ref "IC28") (pin "T1") (pinfunction "VSS_T1") (pintype "power_in"))
      (node (ref "IC28") (pin "T9") (pinfunction "VSS_T9") (pintype "power_in"))
      (node (ref "R127") (pin "2") (pinfunction "2_2") (pintype "passive"))
      (node (ref "R180") (pin "1") (pinfunction "1_1") (pintype "passive"))
      (node (ref "R268") (pin "2") (pinfunction "2_2") (pintype "passive"))
      (node (ref "R270") (pin "1") (pinfunction "1_1") (pintype "passive"))
      (node (ref "R278") (pin "1") (pinfunction "1_1") (pintype "passive"))
      (node (ref "R285") (pin "1") (pinfunction "1_1") (pintype "passive"))
    )
    (net (code "55") (name "Net-(IC19I-IO_L27N_5)") (class "Default")
      (node (ref "IC19") (pin "L25") (pinfunction "IO_L27N_5_L25") (pintype "bidirectional"))
      (node (ref "R127") (pin "1") (pinfunction "1_1") (pintype "passive"))
    )
    (net (code "56") (name "P1V5") (class "Default")
      (node (ref "C383") (pin "2") (pinfunction "2_2") (pintype "passive"))
      (node (ref "C384") (pin "2") (pinfunction "2_2") (pintype "passive"))
      (node (ref "C385") (pin "2") (pinfunction "2_2") (pintype "passive"))
      (node (ref "C388") (pin "2") (pinfunction "2_2") (pintype "passive"))
      (node (ref "C389") (pin "2") (pinfunction "2_2") (pintype "passive"))
      (node (ref "C391") (pin "2") (pinfunction "2_2") (pintype "passive"))
      (node (ref "C394") (pin "2") (pinfunction "2_2") (pintype "passive"))
      (node (ref "C395") (pin "2") (pinfunction "2_2") (pintype "passive"))
      (node (ref "C396") (pin "2") (pinfunction "2_2") (pintype "passive"))
      (node (ref "IC28") (pin "A1") (pinfunction "VDDQ_A1") (pintype "power_in"))
      (node (ref "IC28") (pin "A8") (pinfunction "VDDQ_A8") (pintype "power_in"))
      (node (ref "IC28") (pin "B2") (pinfunction "VDD_B2") (pintype "power_in"))
      (node (ref "IC28") (pin "C1") (pinfunction "VDDQ_C1") (pintype "power_in"))
      (node (ref "IC28") (pin "C9") (pinfunction "VDDQ_C9") (pintype "power_in"))
      (node (ref "IC28") (pin "D2") (pinfunction "VDDQ_D2") (pintype "power_in"))
      (node (ref "IC28") (pin "D9") (pinfunction "VDD_D9") (pintype "power_in"))
      (node (ref "IC28") (pin "E9") (pinfunction "VDDQ_E9") (pintype "power_in"))
      (node (ref "IC28") (pin "F1") (pinfunction "VDDQ_F1") (pintype "power_in"))
      (node (ref "IC28") (pin "G7") (pinfunction "VDD_G7") (pintype "power_in"))
      (node (ref "IC28") (pin "H2") (pinfunction "VDDQ_H2") (pintype "power_in"))
      (node (ref "IC28") (pin "H9") (pinfunction "VDDQ_H9") (pintype "power_in"))
      (node (ref "IC28") (pin "K2") (pinfunction "VDD_K2") (pintype "power_in"))
      (node (ref "IC28") (pin "K8") (pinfunction "VDD_K8") (pintype "power_in"))
      (node (ref "IC28") (pin "N1") (pinfunction "VDD_N1") (pintype "power_in"))
      (node (ref "IC28") (pin "N9") (pinfunction "VDD_N9") (pintype "power_in"))
      (node (ref "IC28") (pin "R1") (pinfunction "VDD_R1") (pintype "power_in"))
      (node (ref "IC28") (pin "R9") (pinfunction "VDD_R9") (pintype "power_in"))
    )
    (net (code "57") (name "VREF_DDR3") (class "Default")
      (node (ref "C242") (pin "2") (pinfunction "2_2") (pintype "passive"))
      (node (ref "C243") (pin "2") (pinfunction "2_2") (pintype "passive"))
      (node (ref "C393") (pin "2") (pinfunction "2_2") (pintype "passive"))
      (node (ref "IC19") (pin "F25") (pinfunction "IO_L1N_A24_VREF_5_F25") (pintype "bidirectional"))
      (node (ref "IC19") (pin "N25") (pinfunction "IO_L26N_VREF_5_N25") (pintype "bidirectional"))
      (node (ref "IC28") (pin "H1") (pinfunction "VREFDQ_H1") (pintype "power_in"))
      (node (ref "IC28") (pin "M8") (pinfunction "VREFCA_M8") (pintype "power_in"))
    )
    (net (code "58") (name "VTT_DDR3") (class "Default")
      (node (ref "C397") (pin "2") (pinfunction "2_2") (pintype "passive"))
      (node (ref "C398") (pin "2") (pinfunction "2_2") (pintype "passive"))
      (node (ref "C399") (pin "2") (pinfunction "2_2") (pintype "passive"))
      (node (ref "C400") (pin "2") (pinfunction "2_2") (pintype "passive"))
      (node (ref "C401") (pin "2") (pinfunction "2_2") (pintype "passive"))
      (node (ref "C402") (pin "2") (pinfunction "2_2") (pintype "passive"))
      (node (ref "C403") (pin "2") (pinfunction "2_2") (pintype "passive"))
      (node (ref "C404") (pin "2") (pinfunction "2_2") (pintype "passive"))
      (node (ref "C405") (pin "2") (pinfunction "2_2") (pintype "passive"))
      (node (ref "C406") (pin "2") (pinfunction "2_2") (pintype "passive"))
      (node (ref "C407") (pin "2") (pinfunction "2_2") (pintype "passive"))
      (node (ref "C408") (pin "2") (pinfunction "2_2") (pintype "passive"))
      (node (ref "C409") (pin "2") (pinfunction "2_2") (pintype "passive"))
      (node (ref "C410") (pin "2") (pinfunction "2_2") (pintype "passive"))
      (node (ref "C411") (pin "2") (pinfunction "2_2") (pintype "passive"))
      (node (ref "R181") (pin "2") (pinfunction "2_2") (pintype "passive"))
      (node (ref "R182") (pin "2") (pinfunction "2_2") (pintype "passive"))
      (node (ref "R261") (pin "2") (pinfunction "2_2") (pintype "passive"))
      (node (ref "R264") (pin "2") (pinfunction "2_2") (pintype "passive"))
      (node (ref "R265") (pin "2") (pinfunction "2_2") (pintype "passive"))
      (node (ref "R266") (pin "2") (pinfunction "2_2") (pintype "passive"))
      (node (ref "R267") (pin "2") (pinfunction "2_2") (pintype "passive"))
      (node (ref "R269") (pin "2") (pinfunction "2_2") (pintype "passive"))
      (node (ref "R271") (pin "2") (pinfunction "2_2") (pintype "passive"))
      (node (ref "R272") (pin "2") (pinfunction "2_2") (pintype "passive"))
      (node (ref "R273") (pin "2") (pinfunction "2_2") (pintype "passive"))
      (node (ref "R280") (pin "2") (pinfunction "2_2") (pintype "passive"))
      (node (ref "R281") (pin "2") (pinfunction "2_2") (pintype "passive"))
      (node (ref "R282") (pin "2") (pinfunction "2_2") (pintype "passive"))
      (node (ref "R283") (pin "2") (pinfunction "2_2") (pintype "passive"))
      (node (ref "R284") (pin "2") (pinfunction "2_2") (pintype "passive"))
      (node (ref "R287") (pin "2") (pinfunction "2_2") (pintype "passive"))
      (node (ref "R288") (pin "2") (pinfunction "2_2") (pintype "passive"))
      (node (ref "R289") (pin "2") (pinfunction "2_2") (pintype "passive"))
      (node (ref "R290") (pin "2") (pinfunction "2_2") (pintype "passive"))
      (node (ref "R292") (pin "2") (pinfunction "2_2") (pintype "passive"))
      (node (ref "R293") (pin "2") (pinfunction "2_2") (pintype "passive"))
      (node (ref "R294") (pin "2") (pinfunction "2_2") (pintype "passive"))
      (node (ref "R295") (pin "2") (pinfunction "2_2") (pintype "passive"))
      (node (ref "R296") (pin "2") (pinfunction "2_2") (pintype "passive"))
      (node (ref "R297") (pin "2") (pinfunction "2_2") (pintype "passive"))
      (node (ref "R298") (pin "2") (pinfunction "2_2") (pintype "passive"))
      (node (ref "R299") (pin "2") (pinfunction "2_2") (pintype "passive"))
      (node (ref "R300") (pin "2") (pinfunction "2_2") (pintype "passive"))
      (node (ref "R301") (pin "2") (pinfunction "2_2") (pintype "passive"))
      (node (ref "R302") (pin "2") (pinfunction "2_2") (pintype "passive"))
      (node (ref "R303") (pin "2") (pinfunction "2_2") (pintype "passive"))
      (node (ref "R304") (pin "2") (pinfunction "2_2") (pintype "passive"))
      (node (ref "R305") (pin "2") (pinfunction "2_2") (pintype "passive"))
      (node (ref "R306") (pin "2") (pinfunction "2_2") (pintype "passive"))
      (node (ref "R307") (pin "2") (pinfunction "2_2") (pintype "passive"))
      (node (ref "R308") (pin "2") (pinfunction "2_2") (pintype "passive"))
      (node (ref "R309") (pin "2") (pinfunction "2_2") (pintype "passive"))
      (node (ref "R310") (pin "2") (pinfunction "2_2") (pintype "passive"))
      (node (ref "R311") (pin "2") (pinfunction "2_2") (pintype "passive"))
      (node (ref "R312") (pin "2") (pinfunction "2_2") (pintype "passive"))
      (node (ref "R313") (pin "2") (pinfunction "2_2") (pintype "passive"))
      (node (ref "R314") (pin "2") (pinfunction "2_2") (pintype "passive"))
    )
    (net (code "59") (name "unconnected-(IC19I-IO_L1P_A25_5-PadG25)") (class "Default")
      (node (ref "IC19") (pin "G25") (pinfunction "IO_L1P_A25_5_G25") (pintype "bidirectional+no_connect"))
    )
    (net (code "60") (name "unconnected-(IC19I-IO_L26P_5-PadN24)") (class "Default")
      (node (ref "IC19") (pin "N24") (pinfunction "IO_L26P_5_N24") (pintype "bidirectional"))
    )
    (net (code "61") (name "unconnected-(IC19I-IO_L27P_5-PadL24)") (class "Default")
      (node (ref "IC19") (pin "L24") (pinfunction "IO_L27P_5_L24") (pintype "bidirectional"))
    )
    (net (code "62") (name "unconnected-(IC28-NC-PadJ1)") (class "Default")
      (node (ref "IC28") (pin "J1") (pinfunction "NC_J1") (pintype "passive+no_connect"))
    )
    (net (code "63") (name "unconnected-(IC28-NC-PadJ9)") (class "Default")
      (node (ref "IC28") (pin "J9") (pinfunction "NC_J9") (pintype "passive+no_connect"))
    )
    (net (code "64") (name "unconnected-(IC28-NC-PadL1)") (class "Default")
      (node (ref "IC28") (pin "L1") (pinfunction "NC_L1") (pintype "passive+no_connect"))
    )
    (net (code "65") (name "unconnected-(IC28-NC-PadL9)") (class "Default")
      (node (ref "IC28") (pin "L9") (pinfunction "NC_L9") (pintype "passive+no_connect"))
    )
    (net (code "66") (name "unconnected-(IC28-NC-PadM7)") (class "Default")
      (node (ref "IC28") (pin "M7") (pinfunction "NC_M7") (pintype "passive+no_connect"))
    )
  )
)
